# LB_o1_LED-v03_rev2.net
KiCad netlist of a schematic drawn in EAGLE
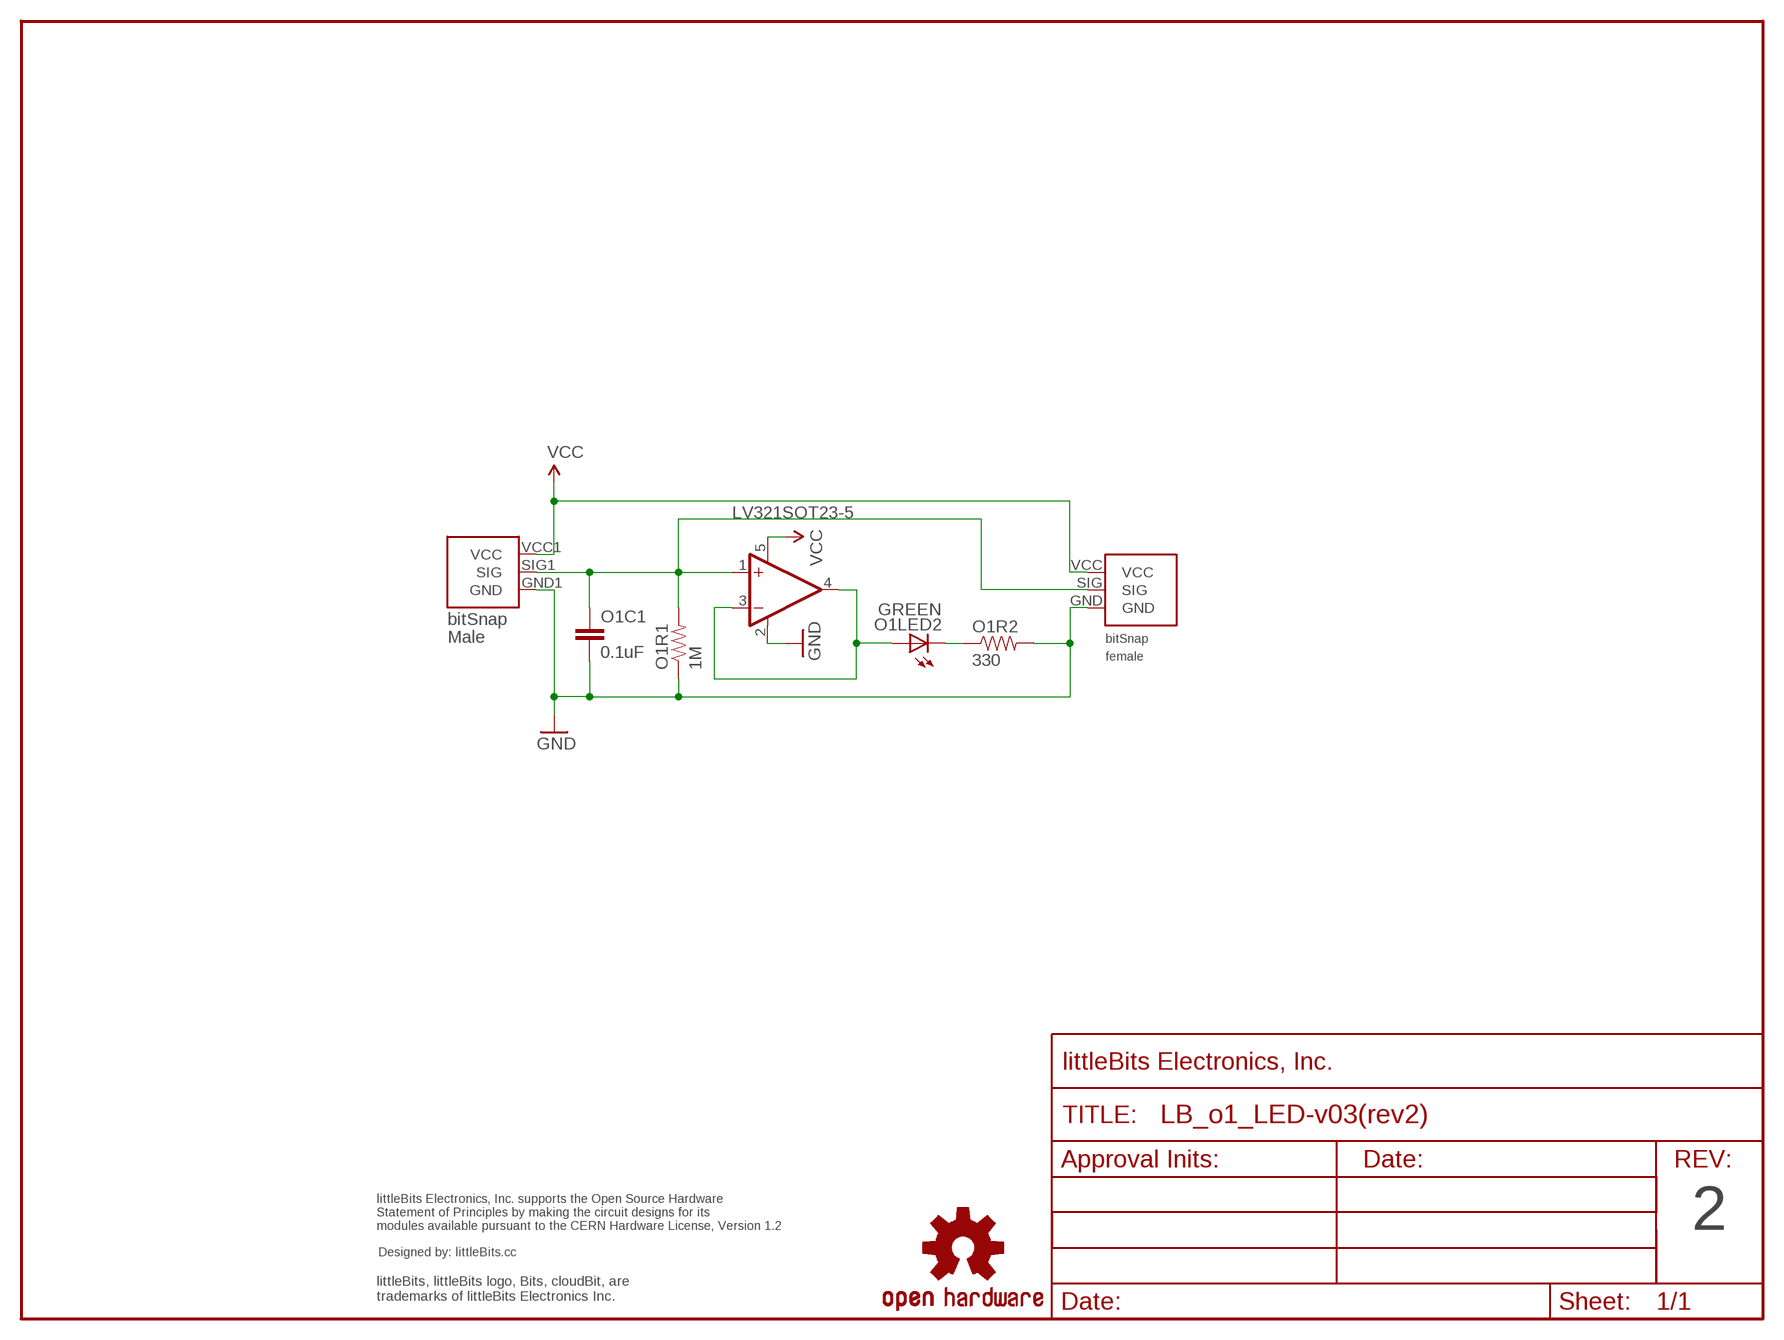
[diagram p0: schematic, sheet 1]

(export (version "E")
  (design (tool "Eeschema 10.0.6"))
  (components
    (comp (ref "O1BSF")
      (value "BITSNAP_V03_FEMALE")
      (footprint "eagle-import:BITSNAP_V03_FEMALE")
      (libsource (lib "eagle-import") (part "BITSNAP_V03_FEMALE"))
    )
    (comp (ref "O1BSM")
      (value "BITSNAP_V03_MALE")
      (footprint "eagle-import:BITSNAP_V03_MALE")
      (libsource (lib "eagle-import") (part "BITSNAP_V03_MALE"))
    )
    (comp (ref "O1C1")
      (value "0.1uF")
      (footprint "eagle-import:0603-CAP")
      (libsource (lib "eagle-import") (part "CAP0603-CAP"))
    )
    (comp (ref "O1LED2")
      (value "GREEN")
      (footprint "eagle-import:LED-1206")
      (libsource (lib "eagle-import") (part "LED1206"))
    )
    (comp (ref "O1R1")
      (value "1M")
      (footprint "eagle-import:0603-RES")
      (libsource (lib "eagle-import") (part "RESISTOR0603-RES"))
    )
    (comp (ref "O1R2")
      (value "330")
      (footprint "eagle-import:0603-RES")
      (libsource (lib "eagle-import") (part "RESISTOR0603-RES"))
    )
    (comp (ref "O1U1")
      (value "LV321SOT23-5")
      (footprint "eagle-import:SOT23-5")
      (libsource (lib "eagle-import") (part "LV321SOT23-5"))
    )
    (comp (ref "U$1")
      (value "OSHWCREDIT")
      (footprint "eagle-import:OSHWCREDIT")
      (libsource (lib "eagle-import") (part "OSHWCREDIT"))
    )
    (comp (ref "U$3")
      (value "OSHW-LOGOL")
      (footprint "eagle-import:OSHW-LOGO-L")
      (libsource (lib "eagle-import") (part "OSHW-LOGOL"))
    )
    (comp (ref "U$4")
      (value "FRAME-LETTER-OHWOHW")
      (footprint "eagle-import:FABDWG01-OHW")
      (libsource (lib "eagle-import") (part "FRAME-LETTER-OHWOHW"))
    )
  )
  (nets
    (net (code "1") (name "GND") (class "Default")
      (node (ref "O1BSF") (pin "GND") (pinfunction "GND_GND") (pintype "bidirectional"))
      (node (ref "O1BSM") (pin "GND1") (pinfunction "GND_GND1") (pintype "bidirectional"))
      (node (ref "O1C1") (pin "2") (pinfunction "2_2") (pintype "passive"))
      (node (ref "O1R1") (pin "1") (pinfunction "1_1") (pintype "passive"))
      (node (ref "O1R2") (pin "2") (pinfunction "2_2") (pintype "passive"))
      (node (ref "O1U1") (pin "2") (pinfunction "V-_2") (pintype "power_in"))
    )
    (net (code "2") (name "Net-(O1BSM-SIG)") (class "Default")
      (node (ref "O1BSF") (pin "SIG") (pinfunction "SIG_SIG") (pintype "bidirectional"))
      (node (ref "O1BSM") (pin "SIG1") (pinfunction "SIG_SIG1") (pintype "bidirectional"))
      (node (ref "O1C1") (pin "1") (pinfunction "1_1") (pintype "passive"))
      (node (ref "O1R1") (pin "2") (pinfunction "2_2") (pintype "passive"))
      (node (ref "O1U1") (pin "1") (pinfunction "+IN_1") (pintype "input"))
    )
    (net (code "3") (name "Net-(O1LED2-PadC)") (class "Default")
      (node (ref "O1LED2") (pin "C") (pinfunction "C_C") (pintype "passive"))
      (node (ref "O1R2") (pin "1") (pinfunction "1_1") (pintype "passive"))
    )
    (net (code "4") (name "Net-(O1U1--IN)") (class "Default")
      (node (ref "O1LED2") (pin "A") (pinfunction "A_A") (pintype "passive"))
      (node (ref "O1U1") (pin "3") (pinfunction "-IN_3") (pintype "input"))
      (node (ref "O1U1") (pin "4") (pinfunction "OUT_4") (pintype "output"))
    )
    (net (code "5") (name "VCC") (class "Default")
      (node (ref "O1BSF") (pin "VCC") (pinfunction "VCC_VCC") (pintype "bidirectional"))
      (node (ref "O1BSM") (pin "VCC1") (pinfunction "VCC_VCC1") (pintype "bidirectional"))
      (node (ref "O1U1") (pin "5") (pinfunction "V+_5") (pintype "power_in"))
    )
  )
)
